# ownduino.net
KiCad netlist of a schematic drawn in EAGLE
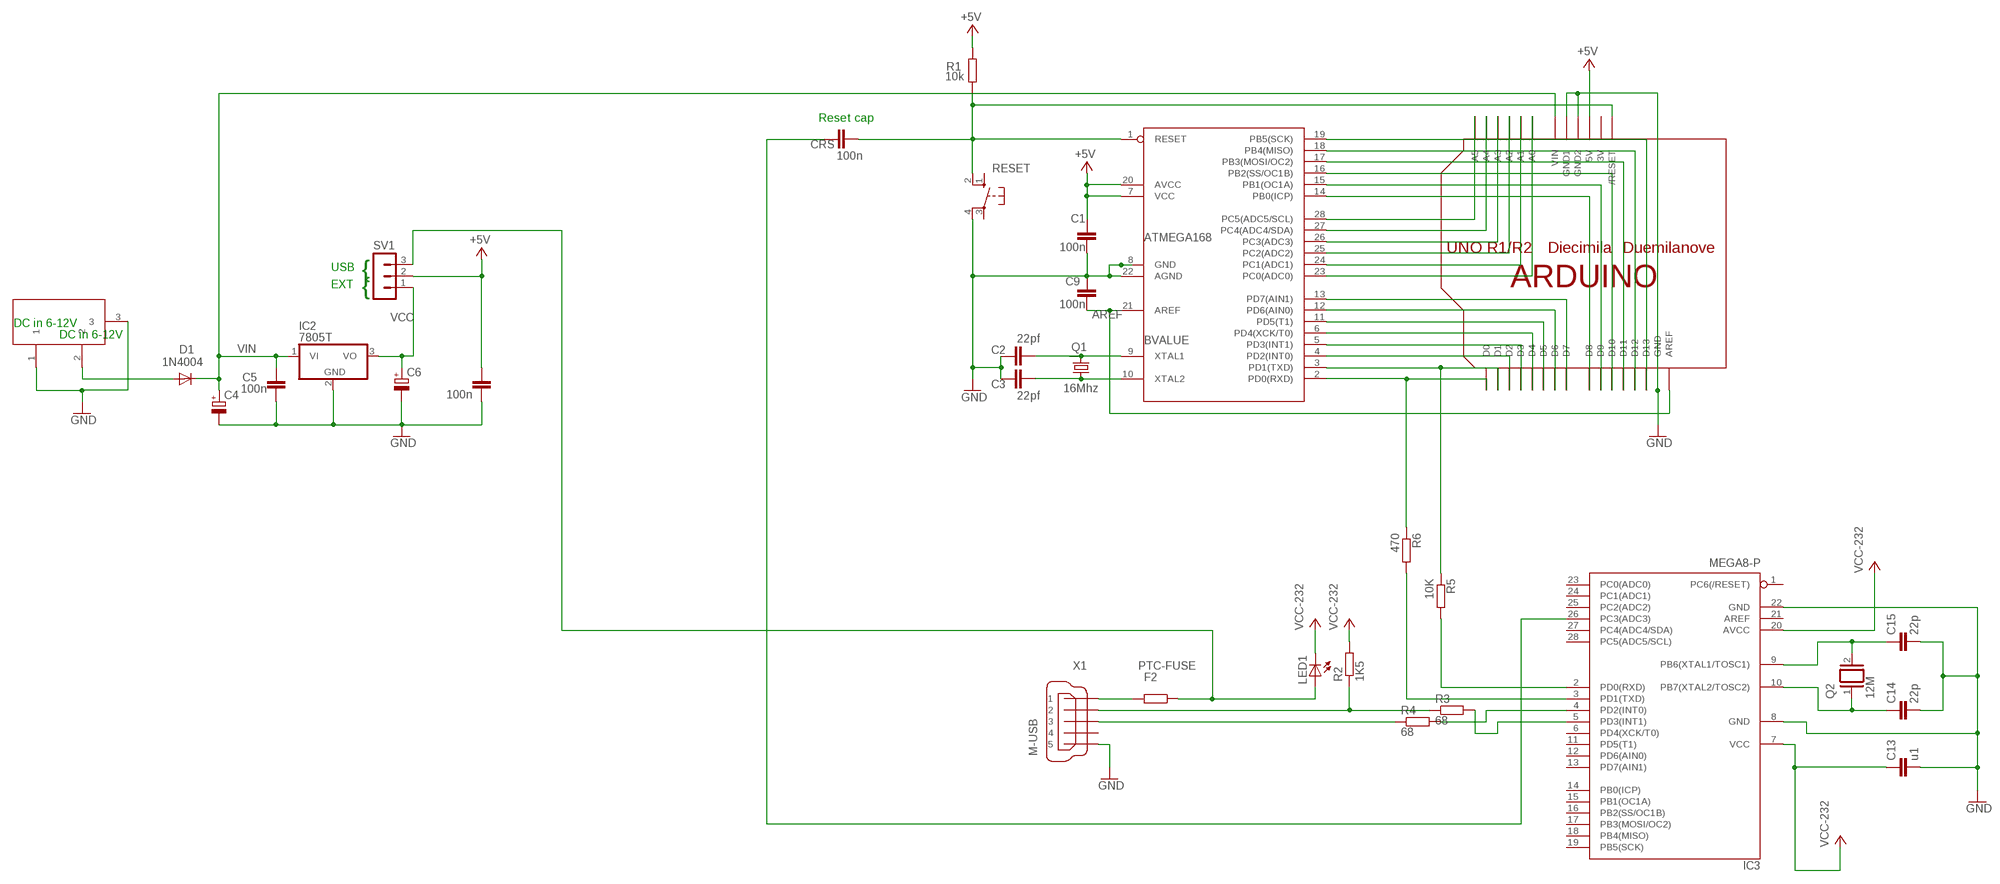
[diagram p0: schematic, sheet 1]

(export (version "E")
  (design (tool "Eeschema 10.0.6"))
  (components
    (comp (ref "BVALUE")
      (value "ATMEGA168")
      (footprint "eagle-import:DIL28-3")
      (libsource (lib "eagle-import") (part "my-library_MEGA8-P"))
    )
    (comp (ref "C1")
      (value "100n")
      (footprint "eagle-import:C025-024X044")
      (libsource (lib "eagle-import") (part "C-EU025-024X044"))
    )
    (comp (ref "C2")
      (value "22pf")
      (footprint "eagle-import:C025-024X044")
      (libsource (lib "eagle-import") (part "C-EU025-024X044"))
    )
    (comp (ref "C3")
      (value "22pf")
      (footprint "eagle-import:C025-024X044")
      (libsource (lib "eagle-import") (part "C-EU025-024X044"))
    )
    (comp (ref "C4")
      (value "CPOL-EUE2.5-6")
      (footprint "eagle-import:E2,5-6")
      (libsource (lib "eagle-import") (part "CPOL-EUE2.5-6"))
    )
    (comp (ref "C5")
      (value "100n")
      (footprint "eagle-import:C025-024X044")
      (libsource (lib "eagle-import") (part "C-EU025-024X044"))
    )
    (comp (ref "C6")
      (value "CPOL-EUE2.5-6")
      (footprint "eagle-import:E2,5-6")
      (libsource (lib "eagle-import") (part "CPOL-EUE2.5-6"))
    )
    (comp (ref "C9")
      (value "100n")
      (footprint "eagle-import:C025-024X044")
      (libsource (lib "eagle-import") (part "C-EU025-024X044"))
    )
    (comp (ref "C10")
      (value "100n")
      (footprint "eagle-import:C025-024X044")
      (libsource (lib "eagle-import") (part "C-EU025-024X044"))
    )
    (comp (ref "C13")
      (value "u1")
      (footprint "eagle-import:C025-024X044")
      (libsource (lib "eagle-import") (part "C-EU025-024X044"))
    )
    (comp (ref "C14")
      (value "22p")
      (footprint "eagle-import:C025-024X044")
      (libsource (lib "eagle-import") (part "C-EU025-024X044"))
    )
    (comp (ref "C15")
      (value "22p")
      (footprint "eagle-import:C025-024X044")
      (libsource (lib "eagle-import") (part "C-EU025-024X044"))
    )
    (comp (ref "CRS")
      (value "100n")
      (footprint "eagle-import:C025-024X044")
      (libsource (lib "eagle-import") (part "C-EU025-024X044"))
    )
    (comp (ref "D1")
      (value "1N4004")
      (footprint "eagle-import:DIODE-0.4")
      (libsource (lib "eagle-import") (part "DIODEPTH"))
    )
    (comp (ref "DC1")
      (value "9V in")
      (footprint "eagle-import:DC-21MM")
      (libsource (lib "eagle-import") (part "DC21MMX"))
    )
    (comp (ref "F2")
      (value "PTC-FUSE")
      (footprint "eagle-import:0204_5")
      (libsource (lib "eagle-import") (part "R-EU_0204/5"))
    )
    (comp (ref "IC2")
      (value "7805T")
      (footprint "eagle-import:TO220H")
      (libsource (lib "eagle-import") (part "78T05"))
    )
    (comp (ref "IC3")
      (value "MEGA8-P")
      (footprint "eagle-import:DIL28-3")
      (libsource (lib "eagle-import") (part "MEGA8-P"))
    )
    (comp (ref "LED1")
      (value "LED3MM")
      (footprint "eagle-import:LED3MM")
      (libsource (lib "eagle-import") (part "LED3MM"))
    )
    (comp (ref "Q1")
      (value "16Mhz")
      (footprint "eagle-import:HC49U-V")
      (libsource (lib "eagle-import") (part "CRYSTALHC49U-V"))
    )
    (comp (ref "Q2")
      (value "12M")
      (footprint "eagle-import:QS")
      (libsource (lib "eagle-import") (part "XTAL/S"))
    )
    (comp (ref "R1")
      (value "10k")
      (footprint "eagle-import:0204_7")
      (libsource (lib "eagle-import") (part "R-EU_0204/7"))
    )
    (comp (ref "R2")
      (value "1K5")
      (footprint "eagle-import:0204V")
      (libsource (lib "eagle-import") (part "R-EU_0204/2V"))
    )
    (comp (ref "R3")
      (value "68")
      (footprint "eagle-import:0204V")
      (libsource (lib "eagle-import") (part "R-EU_0204/2V"))
    )
    (comp (ref "R4")
      (value "68")
      (footprint "eagle-import:0204_5")
      (libsource (lib "eagle-import") (part "R-EU_0204/5"))
    )
    (comp (ref "R5")
      (value "10K")
      (footprint "eagle-import:0204_7")
      (libsource (lib "eagle-import") (part "R-EU_0204/7"))
    )
    (comp (ref "R6")
      (value "470")
      (footprint "eagle-import:0204_7")
      (libsource (lib "eagle-import") (part "R-EU_0204/7"))
    )
    (comp (ref "RESET")
      (value "10-XX")
      (footprint "eagle-import:B3F-10XX")
      (libsource (lib "eagle-import") (part "10-XX"))
    )
    (comp (ref "SV1")
      (value "MA03-1")
      (footprint "eagle-import:MA03-1")
      (libsource (lib "eagle-import") (part "MA03-1"))
    )
    (comp (ref "U$1")
      (value "ARDUINOUNO")
      (footprint "eagle-import:ARDUINO")
      (libsource (lib "eagle-import") (part "ARDUINOUNO"))
    )
    (comp (ref "X1")
      (value "M-USB")
      (footprint "eagle-import:32005-601")
      (libsource (lib "eagle-import") (part "MINI-USB_SHIELD5P2-32005-601"))
    )
  )
  (nets
    (net (code "1") (name "+5V") (class "Default")
      (node (ref "BVALUE") (pin "20") (pinfunction "AVCC_20") (pintype "bidirectional"))
      (node (ref "BVALUE") (pin "7") (pinfunction "VCC_7") (pintype "bidirectional"))
      (node (ref "C1") (pin "1") (pinfunction "1_1") (pintype "passive"))
      (node (ref "C10") (pin "2") (pinfunction "2_2") (pintype "passive"))
      (node (ref "R1") (pin "2") (pinfunction "2_2") (pintype "passive"))
      (node (ref "SV1") (pin "2") (pinfunction "2_2") (pintype "passive"))
      (node (ref "U$1") (pin "5V") (pinfunction "5V_5V") (pintype "power_in"))
    )
    (net (code "2") (name "/3V") (class "Default")
      (node (ref "U$1") (pin "3V") (pinfunction "3V_3V") (pintype "power_in"))
    )
    (net (code "3") (name "/AREF") (class "Default")
      (node (ref "BVALUE") (pin "21") (pinfunction "AREF_21") (pintype "bidirectional"))
      (node (ref "C9") (pin "1") (pinfunction "1_1") (pintype "passive"))
      (node (ref "U$1") (pin "AREF") (pinfunction "AREF_AREF") (pintype "bidirectional"))
    )
    (net (code "4") (name "/VIN") (class "Default")
      (node (ref "C4") (pin "+") (pinfunction "+_+") (pintype "passive"))
      (node (ref "C5") (pin "2") (pinfunction "2_2") (pintype "passive"))
      (node (ref "D1") (pin "C") (pinfunction "C_C") (pintype "passive"))
      (node (ref "IC2") (pin "1") (pinfunction "VI_1") (pintype "input"))
      (node (ref "U$1") (pin "VIN") (pinfunction "VIN_VIN") (pintype "power_in"))
    )
    (net (code "5") (name "GND") (class "Default")
      (node (ref "BVALUE") (pin "22") (pinfunction "AGND_22") (pintype "bidirectional"))
      (node (ref "BVALUE") (pin "8") (pinfunction "GND_8") (pintype "bidirectional"))
      (node (ref "C1") (pin "2") (pinfunction "2_2") (pintype "passive"))
      (node (ref "C10") (pin "1") (pinfunction "1_1") (pintype "passive"))
      (node (ref "C13") (pin "2") (pinfunction "2_2") (pintype "passive"))
      (node (ref "C14") (pin "2") (pinfunction "2_2") (pintype "passive"))
      (node (ref "C15") (pin "2") (pinfunction "2_2") (pintype "passive"))
      (node (ref "C2") (pin "1") (pinfunction "1_1") (pintype "passive"))
      (node (ref "C3") (pin "1") (pinfunction "1_1") (pintype "passive"))
      (node (ref "C4") (pin "-") (pinfunction "-_-") (pintype "passive"))
      (node (ref "C5") (pin "1") (pinfunction "1_1") (pintype "passive"))
      (node (ref "C6") (pin "-") (pinfunction "-_-") (pintype "passive"))
      (node (ref "C9") (pin "2") (pinfunction "2_2") (pintype "passive"))
      (node (ref "DC1") (pin "1") (pinfunction "1_1") (pintype "power_in"))
      (node (ref "DC1") (pin "3") (pinfunction "3_3") (pintype "power_in"))
      (node (ref "IC2") (pin "2") (pinfunction "GND_2") (pintype "passive"))
      (node (ref "IC3") (pin "22") (pinfunction "GND_22") (pintype "power_in"))
      (node (ref "IC3") (pin "8") (pinfunction "GND_8") (pintype "power_in"))
      (node (ref "RESET") (pin "4") (pinfunction "P1_4") (pintype "passive"))
      (node (ref "U$1") (pin "GND") (pinfunction "GND_GND") (pintype "power_in"))
      (node (ref "U$1") (pin "GND1") (pinfunction "GND1_GND1") (pintype "power_in"))
      (node (ref "U$1") (pin "GND2") (pinfunction "GND2_GND2") (pintype "power_in"))
      (node (ref "X1") (pin "5") (pinfunction "5_5") (pintype "passive"))
    )
    (net (code "6") (name "Net-(BVALUE-PB0(ICP))") (class "Default")
      (node (ref "BVALUE") (pin "14") (pinfunction "PB0(ICP)_14") (pintype "bidirectional"))
      (node (ref "U$1") (pin "D8") (pinfunction "D8_D8") (pintype "bidirectional"))
    )
    (net (code "7") (name "Net-(BVALUE-PB1(OC1A))") (class "Default")
      (node (ref "BVALUE") (pin "15") (pinfunction "PB1(OC1A)_15") (pintype "bidirectional"))
      (node (ref "U$1") (pin "D9") (pinfunction "D9_D9") (pintype "bidirectional"))
    )
    (net (code "8") (name "Net-(BVALUE-PB2(SS{slash}OC1B))") (class "Default")
      (node (ref "BVALUE") (pin "16") (pinfunction "PB2(SS/OC1B)_16") (pintype "bidirectional"))
      (node (ref "U$1") (pin "D10") (pinfunction "D10_D10") (pintype "bidirectional"))
    )
    (net (code "9") (name "Net-(BVALUE-PB3(MOSI{slash}OC2))") (class "Default")
      (node (ref "BVALUE") (pin "17") (pinfunction "PB3(MOSI/OC2)_17") (pintype "bidirectional"))
      (node (ref "U$1") (pin "D11") (pinfunction "D11_D11") (pintype "bidirectional"))
    )
    (net (code "10") (name "Net-(BVALUE-PB4(MISO))") (class "Default")
      (node (ref "BVALUE") (pin "18") (pinfunction "PB4(MISO)_18") (pintype "bidirectional"))
      (node (ref "U$1") (pin "D12") (pinfunction "D12_D12") (pintype "bidirectional"))
    )
    (net (code "11") (name "Net-(BVALUE-PB5(SCK))") (class "Default")
      (node (ref "BVALUE") (pin "19") (pinfunction "PB5(SCK)_19") (pintype "bidirectional"))
      (node (ref "U$1") (pin "D13") (pinfunction "D13_D13") (pintype "bidirectional"))
    )
    (net (code "12") (name "Net-(BVALUE-PC0(ADC0))") (class "Default")
      (node (ref "BVALUE") (pin "23") (pinfunction "PC0(ADC0)_23") (pintype "bidirectional"))
      (node (ref "U$1") (pin "A0") (pinfunction "A0_A0") (pintype "bidirectional"))
    )
    (net (code "13") (name "Net-(BVALUE-PC1(ADC1))") (class "Default")
      (node (ref "BVALUE") (pin "24") (pinfunction "PC1(ADC1)_24") (pintype "bidirectional"))
      (node (ref "U$1") (pin "A1") (pinfunction "A1_A1") (pintype "bidirectional"))
    )
    (net (code "14") (name "Net-(BVALUE-PC2(ADC2))") (class "Default")
      (node (ref "BVALUE") (pin "25") (pinfunction "PC2(ADC2)_25") (pintype "bidirectional"))
      (node (ref "U$1") (pin "A2") (pinfunction "A2_A2") (pintype "bidirectional"))
    )
    (net (code "15") (name "Net-(BVALUE-PC3(ADC3))") (class "Default")
      (node (ref "BVALUE") (pin "26") (pinfunction "PC3(ADC3)_26") (pintype "bidirectional"))
      (node (ref "U$1") (pin "A3") (pinfunction "A3_A3") (pintype "bidirectional"))
    )
    (net (code "16") (name "Net-(BVALUE-PC4(ADC4{slash}SDA))") (class "Default")
      (node (ref "BVALUE") (pin "27") (pinfunction "PC4(ADC4/SDA)_27") (pintype "bidirectional"))
      (node (ref "U$1") (pin "A4") (pinfunction "A4_A4") (pintype "bidirectional"))
    )
    (net (code "17") (name "Net-(BVALUE-PC5(ADC5{slash}SCL))") (class "Default")
      (node (ref "BVALUE") (pin "28") (pinfunction "PC5(ADC5/SCL)_28") (pintype "bidirectional"))
      (node (ref "U$1") (pin "A5") (pinfunction "A5_A5") (pintype "bidirectional"))
    )
    (net (code "18") (name "Net-(BVALUE-PD0(RXD))") (class "Default")
      (node (ref "BVALUE") (pin "2") (pinfunction "PD0(RXD)_2") (pintype "bidirectional"))
      (node (ref "R6") (pin "1") (pinfunction "1_1") (pintype "passive"))
      (node (ref "U$1") (pin "D0") (pinfunction "D0_D0") (pintype "bidirectional"))
    )
    (net (code "19") (name "Net-(BVALUE-PD1(TXD))") (class "Default")
      (node (ref "BVALUE") (pin "3") (pinfunction "PD1(TXD)_3") (pintype "bidirectional"))
      (node (ref "R5") (pin "1") (pinfunction "1_1") (pintype "passive"))
      (node (ref "U$1") (pin "D1") (pinfunction "D1_D1") (pintype "bidirectional"))
    )
    (net (code "20") (name "Net-(BVALUE-PD2(INT0))") (class "Default")
      (node (ref "BVALUE") (pin "4") (pinfunction "PD2(INT0)_4") (pintype "bidirectional"))
      (node (ref "U$1") (pin "D2") (pinfunction "D2_D2") (pintype "bidirectional"))
    )
    (net (code "21") (name "Net-(BVALUE-PD3(INT1))") (class "Default")
      (node (ref "BVALUE") (pin "5") (pinfunction "PD3(INT1)_5") (pintype "bidirectional"))
      (node (ref "U$1") (pin "D3") (pinfunction "D3_D3") (pintype "bidirectional"))
    )
    (net (code "22") (name "Net-(BVALUE-PD4(XCK{slash}T0))") (class "Default")
      (node (ref "BVALUE") (pin "6") (pinfunction "PD4(XCK/T0)_6") (pintype "bidirectional"))
      (node (ref "U$1") (pin "D4") (pinfunction "D4_D4") (pintype "bidirectional"))
    )
    (net (code "23") (name "Net-(BVALUE-PD5(T1))") (class "Default")
      (node (ref "BVALUE") (pin "11") (pinfunction "PD5(T1)_11") (pintype "bidirectional"))
      (node (ref "U$1") (pin "D5") (pinfunction "D5_D5") (pintype "bidirectional"))
    )
    (net (code "24") (name "Net-(BVALUE-PD6(AIN0))") (class "Default")
      (node (ref "BVALUE") (pin "12") (pinfunction "PD6(AIN0)_12") (pintype "bidirectional"))
      (node (ref "U$1") (pin "D6") (pinfunction "D6_D6") (pintype "bidirectional"))
    )
    (net (code "25") (name "Net-(BVALUE-PD7(AIN1))") (class "Default")
      (node (ref "BVALUE") (pin "13") (pinfunction "PD7(AIN1)_13") (pintype "bidirectional"))
      (node (ref "U$1") (pin "D7") (pinfunction "D7_D7") (pintype "bidirectional"))
    )
    (net (code "26") (name "Net-(BVALUE-RESET)") (class "Default")
      (node (ref "BVALUE") (pin "1") (pinfunction "RESET_1") (pintype "bidirectional"))
      (node (ref "CRS") (pin "2") (pinfunction "2_2") (pintype "passive"))
      (node (ref "R1") (pin "1") (pinfunction "1_1") (pintype "passive"))
      (node (ref "RESET") (pin "2") (pinfunction "S1_2") (pintype "passive"))
      (node (ref "U$1") (pin "RESET") (pinfunction "/RESET_RESET") (pintype "bidirectional"))
    )
    (net (code "27") (name "Net-(BVALUE-XTAL1)") (class "Default")
      (node (ref "BVALUE") (pin "9") (pinfunction "XTAL1_9") (pintype "bidirectional"))
      (node (ref "C2") (pin "2") (pinfunction "2_2") (pintype "passive"))
      (node (ref "Q1") (pin "2") (pinfunction "2_2") (pintype "passive"))
    )
    (net (code "28") (name "Net-(BVALUE-XTAL2)") (class "Default")
      (node (ref "BVALUE") (pin "10") (pinfunction "XTAL2_10") (pintype "bidirectional"))
      (node (ref "C3") (pin "2") (pinfunction "2_2") (pintype "passive"))
      (node (ref "Q1") (pin "1") (pinfunction "1_1") (pintype "passive"))
    )
    (net (code "29") (name "Net-(D1-PadA)") (class "Default")
      (node (ref "D1") (pin "A") (pinfunction "A_A") (pintype "passive"))
      (node (ref "DC1") (pin "2") (pinfunction "2_2") (pintype "power_in"))
    )
    (net (code "30") (name "Net-(F2-Pad1)") (class "Default")
      (node (ref "F2") (pin "1") (pinfunction "1_1") (pintype "passive"))
      (node (ref "LED1") (pin "A") (pinfunction "A_A") (pintype "passive"))
      (node (ref "SV1") (pin "3") (pinfunction "3_3") (pintype "passive"))
    )
    (net (code "31") (name "Net-(F2-Pad2)") (class "Default")
      (node (ref "F2") (pin "2") (pinfunction "2_2") (pintype "passive"))
      (node (ref "X1") (pin "1") (pinfunction "1_1") (pintype "passive"))
    )
    (net (code "32") (name "Net-(IC3-PB6(XTAL1{slash}TOSC1))") (class "Default")
      (node (ref "C15") (pin "1") (pinfunction "1_1") (pintype "passive"))
      (node (ref "IC3") (pin "9") (pinfunction "PB6(XTAL1/TOSC1)_9") (pintype "bidirectional"))
      (node (ref "Q2") (pin "2") (pinfunction "2_2") (pintype "passive"))
    )
    (net (code "33") (name "Net-(IC3-PB7(XTAL2{slash}TOSC2))") (class "Default")
      (node (ref "C14") (pin "1") (pinfunction "1_1") (pintype "passive"))
      (node (ref "IC3") (pin "10") (pinfunction "PB7(XTAL2/TOSC2)_10") (pintype "bidirectional"))
      (node (ref "Q2") (pin "1") (pinfunction "1_1") (pintype "passive"))
    )
    (net (code "34") (name "Net-(IC3-PC3(ADC3))") (class "Default")
      (node (ref "CRS") (pin "1") (pinfunction "1_1") (pintype "passive"))
      (node (ref "IC3") (pin "26") (pinfunction "PC3(ADC3)_26") (pintype "bidirectional"))
    )
    (net (code "35") (name "Net-(IC3-PD0(RXD))") (class "Default")
      (node (ref "IC3") (pin "2") (pinfunction "PD0(RXD)_2") (pintype "bidirectional"))
      (node (ref "R5") (pin "2") (pinfunction "2_2") (pintype "passive"))
    )
    (net (code "36") (name "Net-(IC3-PD1(TXD))") (class "Default")
      (node (ref "IC3") (pin "3") (pinfunction "PD1(TXD)_3") (pintype "bidirectional"))
      (node (ref "R6") (pin "2") (pinfunction "2_2") (pintype "passive"))
    )
    (net (code "37") (name "Net-(IC3-PD2(INT0))") (class "Default")
      (node (ref "IC3") (pin "4") (pinfunction "PD2(INT0)_4") (pintype "bidirectional"))
      (node (ref "R4") (pin "2") (pinfunction "2_2") (pintype "passive"))
    )
    (net (code "38") (name "Net-(IC3-PD3(INT1))") (class "Default")
      (node (ref "IC3") (pin "5") (pinfunction "PD3(INT1)_5") (pintype "bidirectional"))
      (node (ref "R3") (pin "2") (pinfunction "2_2") (pintype "passive"))
    )
    (net (code "39") (name "Net-(R2-Pad1)") (class "Default")
      (node (ref "R2") (pin "1") (pinfunction "1_1") (pintype "passive"))
      (node (ref "R3") (pin "1") (pinfunction "1_1") (pintype "passive"))
      (node (ref "X1") (pin "2") (pinfunction "2_2") (pintype "passive"))
    )
    (net (code "40") (name "Net-(R4-Pad1)") (class "Default")
      (node (ref "R4") (pin "1") (pinfunction "1_1") (pintype "passive"))
      (node (ref "X1") (pin "3") (pinfunction "3_3") (pintype "passive"))
    )
    (net (code "41") (name "VCC-232") (class "Default")
      (node (ref "C13") (pin "1") (pinfunction "1_1") (pintype "passive"))
      (node (ref "C6") (pin "+") (pinfunction "+_+") (pintype "passive"))
      (node (ref "IC2") (pin "3") (pinfunction "VO_3") (pintype "passive"))
      (node (ref "IC3") (pin "20") (pinfunction "AVCC_20") (pintype "power_in"))
      (node (ref "IC3") (pin "7") (pinfunction "VCC_7") (pintype "power_in"))
      (node (ref "LED1") (pin "K") (pinfunction "C_K") (pintype "passive"))
      (node (ref "R2") (pin "2") (pinfunction "2_2") (pintype "passive"))
      (node (ref "SV1") (pin "1") (pinfunction "1_1") (pintype "passive"))
    )
    (net (code "42") (name "unconnected-(IC3-AREF-Pad21)") (class "Default")
      (node (ref "IC3") (pin "21") (pinfunction "AREF_21") (pintype "passive"))
    )
    (net (code "43") (name "unconnected-(IC3-PB0(ICP)-Pad14)") (class "Default")
      (node (ref "IC3") (pin "14") (pinfunction "PB0(ICP)_14") (pintype "bidirectional"))
    )
    (net (code "44") (name "unconnected-(IC3-PB1(OC1A)-Pad15)") (class "Default")
      (node (ref "IC3") (pin "15") (pinfunction "PB1(OC1A)_15") (pintype "bidirectional"))
    )
    (net (code "45") (name "unconnected-(IC3-PB2(SS{slash}OC1B)-Pad16)") (class "Default")
      (node (ref "IC3") (pin "16") (pinfunction "PB2(SS/OC1B)_16") (pintype "bidirectional"))
    )
    (net (code "46") (name "unconnected-(IC3-PB3(MOSI{slash}OC2)-Pad17)") (class "Default")
      (node (ref "IC3") (pin "17") (pinfunction "PB3(MOSI/OC2)_17") (pintype "bidirectional"))
    )
    (net (code "47") (name "unconnected-(IC3-PB4(MISO)-Pad18)") (class "Default")
      (node (ref "IC3") (pin "18") (pinfunction "PB4(MISO)_18") (pintype "bidirectional"))
    )
    (net (code "48") (name "unconnected-(IC3-PB5(SCK)-Pad19)") (class "Default")
      (node (ref "IC3") (pin "19") (pinfunction "PB5(SCK)_19") (pintype "bidirectional"))
    )
    (net (code "49") (name "unconnected-(IC3-PC0(ADC0)-Pad23)") (class "Default")
      (node (ref "IC3") (pin "23") (pinfunction "PC0(ADC0)_23") (pintype "bidirectional"))
    )
    (net (code "50") (name "unconnected-(IC3-PC1(ADC1)-Pad24)") (class "Default")
      (node (ref "IC3") (pin "24") (pinfunction "PC1(ADC1)_24") (pintype "bidirectional"))
    )
    (net (code "51") (name "unconnected-(IC3-PC2(ADC2)-Pad25)") (class "Default")
      (node (ref "IC3") (pin "25") (pinfunction "PC2(ADC2)_25") (pintype "bidirectional"))
    )
    (net (code "52") (name "unconnected-(IC3-PC4(ADC4{slash}SDA)-Pad27)") (class "Default")
      (node (ref "IC3") (pin "27") (pinfunction "PC4(ADC4/SDA)_27") (pintype "bidirectional"))
    )
    (net (code "53") (name "unconnected-(IC3-PC5(ADC5{slash}SCL)-Pad28)") (class "Default")
      (node (ref "IC3") (pin "28") (pinfunction "PC5(ADC5/SCL)_28") (pintype "bidirectional"))
    )
    (net (code "54") (name "unconnected-(IC3-PC6({slash}RESET)-Pad1)") (class "Default")
      (node (ref "IC3") (pin "1") (pinfunction "PC6(/RESET)_1") (pintype "bidirectional"))
    )
    (net (code "55") (name "unconnected-(IC3-PD4(XCK{slash}T0)-Pad6)") (class "Default")
      (node (ref "IC3") (pin "6") (pinfunction "PD4(XCK/T0)_6") (pintype "bidirectional"))
    )
    (net (code "56") (name "unconnected-(IC3-PD5(T1)-Pad11)") (class "Default")
      (node (ref "IC3") (pin "11") (pinfunction "PD5(T1)_11") (pintype "bidirectional"))
    )
    (net (code "57") (name "unconnected-(IC3-PD6(AIN0)-Pad12)") (class "Default")
      (node (ref "IC3") (pin "12") (pinfunction "PD6(AIN0)_12") (pintype "bidirectional"))
    )
    (net (code "58") (name "unconnected-(IC3-PD7(AIN1)-Pad13)") (class "Default")
      (node (ref "IC3") (pin "13") (pinfunction "PD7(AIN1)_13") (pintype "bidirectional"))
    )
    (net (code "59") (name "unconnected-(RESET-P-Pad3)") (class "Default")
      (node (ref "RESET") (pin "3") (pinfunction "P_3") (pintype "passive"))
    )
    (net (code "60") (name "unconnected-(RESET-S-Pad1)") (class "Default")
      (node (ref "RESET") (pin "1") (pinfunction "S_1") (pintype "passive"))
    )
    (net (code "61") (name "unconnected-(X1-Pad4)") (class "Default")
      (node (ref "X1") (pin "4") (pinfunction "4_4") (pintype "passive"))
    )
  )
)
